# schematic.net
KiCad netlist of a schematic drawn in Altium Designer
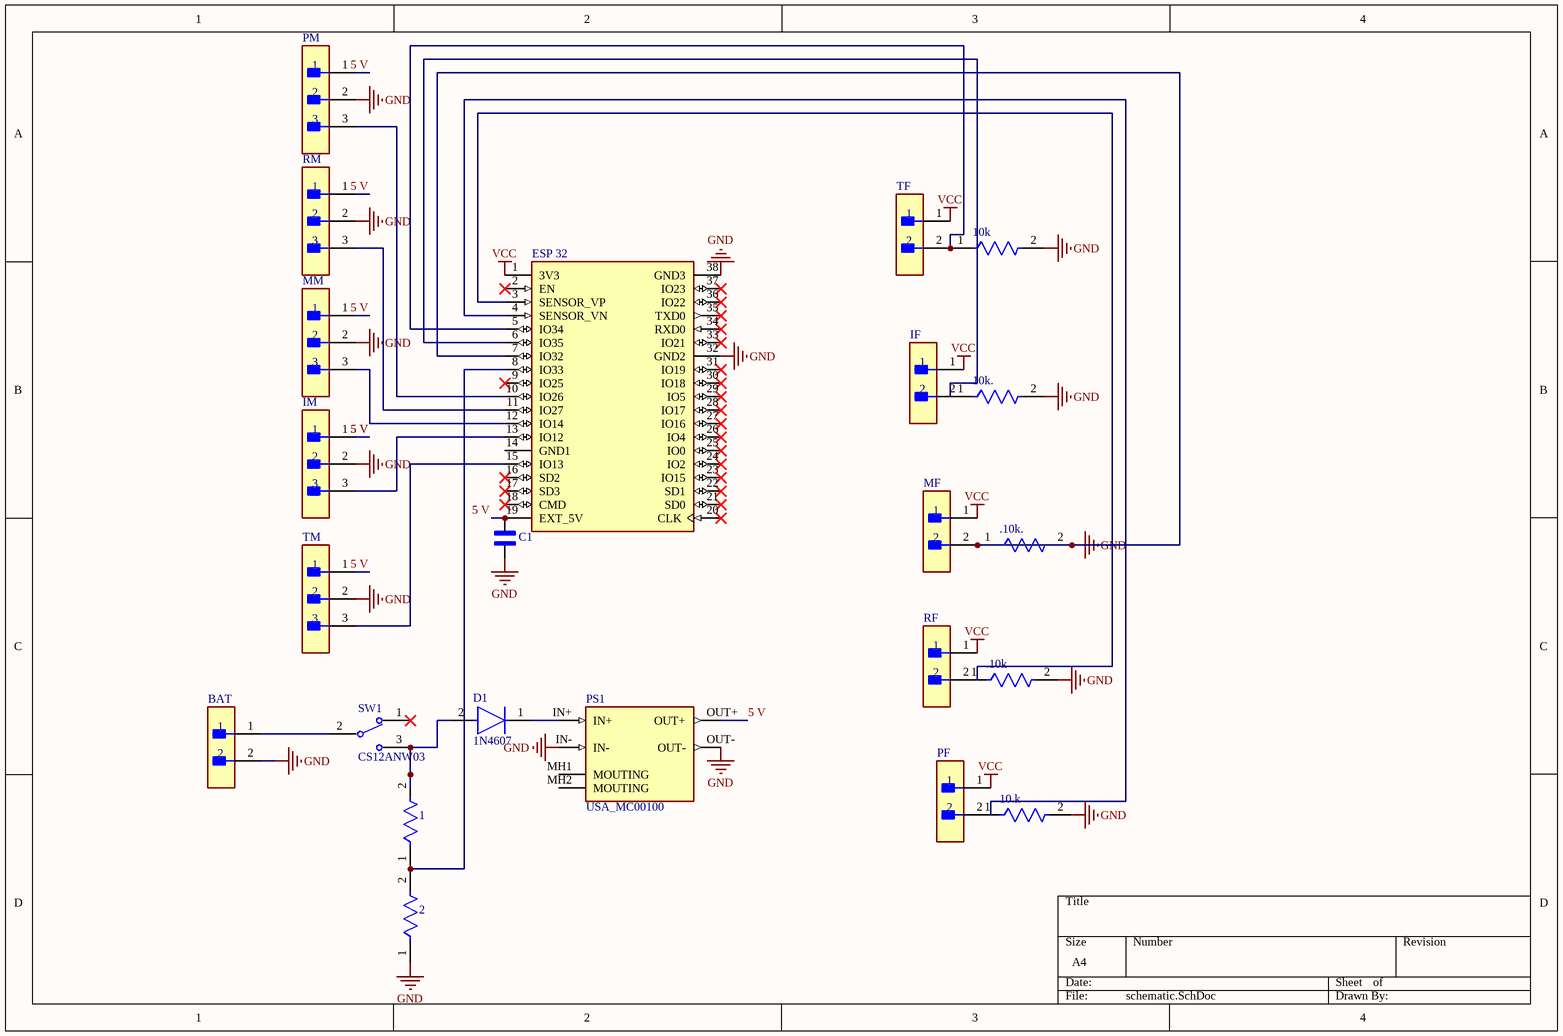
[diagram p0: schematic.SchDoc]

(export (version "E")
  (design (tool "Eeschema 10.0.6"))
  (components
    (comp (ref ".10k")
      (value "VR37000001204JA100")
      (footprint "FP-VR37-MFG")
      (description "RES 1.2M OHM 5% 1/2W AXIAL")
      (fields (field (name "TOLERANCE") "5%"))
      (libsource (lib "Altium Content Vault") (part "1029c3af85768c4190bb7ad29bc67b5"))
    )
    (comp (ref ".10k.")
      (value "VR37000001204JA100")
      (footprint "FP-VR37-MFG")
      (description "RES 1.2M OHM 5% 1/2W AXIAL")
      (fields (field (name "TOLERANCE") "5%"))
      (libsource (lib "Altium Content Vault") (part "1029c3af85768c4190bb7ad29bc67b5"))
    )
    (comp (ref "1")
      (value "VR37000001204JA100")
      (footprint "FP-VR37-MFG")
      (description "RES 1.2M OHM 5% 1/2W AXIAL")
      (fields (field (name "TOLERANCE") "5%"))
      (libsource (lib "Altium Content Vault") (part "1029c3af85768c4190bb7ad29bc67b5"))
    )
    (comp (ref "2")
      (value "VR37000001204JA100")
      (footprint "FP-VR37-MFG")
      (description "RES 1.2M OHM 5% 1/2W AXIAL")
      (fields (field (name "TOLERANCE") "5%"))
      (libsource (lib "Altium Content Vault") (part "1029c3af85768c4190bb7ad29bc67b5"))
    )
    (comp (ref "10.k")
      (value "VR37000001204JA100")
      (footprint "FP-VR37-MFG")
      (description "RES 1.2M OHM 5% 1/2W AXIAL")
      (fields (field (name "TOLERANCE") "5%"))
      (libsource (lib "Altium Content Vault") (part "1029c3af85768c4190bb7ad29bc67b5"))
    )
    (comp (ref "10k")
      (value "VR37000001204JA100")
      (footprint "FP-VR37-MFG")
      (description "RES 1.2M OHM 5% 1/2W AXIAL")
      (fields (field (name "TOLERANCE") "5%"))
      (libsource (lib "Altium Content Vault") (part "1029c3af85768c4190bb7ad29bc67b5"))
    )
    (comp (ref "10k.")
      (value "VR37000001204JA100")
      (footprint "FP-VR37-MFG")
      (description "RES 1.2M OHM 5% 1/2W AXIAL")
      (fields (field (name "TOLERANCE") "5%"))
      (libsource (lib "Altium Content Vault") (part "1029c3af85768c4190bb7ad29bc67b5"))
    )
    (comp (ref "BAT")
      (value "TSW-102-14-G-S")
      (footprint "FP-TSW-102-14-G-S-MFG")
      (description "CONN HEADER VERT 2POS 2.54MM")
      (libsource (lib "Altium Content Vault") (part "88c1139f9d239099ffebecbe3f7647a"))
    )
    (comp (ref "C1")
      (value "FA14X8R1H104KNU06")
      (footprint "CAPRB250W50L450T300H550")
      (description "0.1 ÂµF Â±10% 50V Ceramic Capacitor X8R Radial")
      (fields (field (name "MF") "TDK"))
      (libsource (lib "ceramic capacitor") (part "FA14X8R1H104KNU06"))
    )
    (comp (ref "D1")
      (value "1N4607")
      (footprint "FP-DO-35-MFG")
      (description "1N4607 1N4607 Series 85 V 0.2 A Axial Silicon Switching Diode - DO-35")
      (libsource (lib "Altium Content Vault") (part "1N4607"))
    )
    (comp (ref "ESP 32")
      (value "ESP32-DEVKITC")
      (footprint "MODULE_ESP32-DEVKITC")
      (description "Transceiver; 802.11 b/g/n (Wi-Fi, WiFi, WLAN), BluetoothÂ® Smart Ready 4.x Dual Mode")
      (fields (field (name "MF") "Espressif Systems") (field (name "MP") "ESP32-DEVKITC-32D-F"))
      (libsource (lib "ESP32-DEVKITC") (part "ESP32-DEVKITC"))
    )
    (comp (ref "IF")
      (value "TSW-102-14-G-S")
      (footprint "FP-TSW-102-14-G-S-MFG")
      (description "CONN HEADER VERT 2POS 2.54MM")
      (libsource (lib "Altium Content Vault") (part "88c1139f9d239099ffebecbe3f7647a"))
    )
    (comp (ref "IM")
      (value "NRPN031PAEN-RC")
      (footprint "FP-NRPN031PAEN-RC-MFG")
      (description "CONN HEADER VERT 3POS 2MM")
      (fields
        (field (name "OCTOPART") "https://octopart.com/nrpn031paen-rc-sullins-12817732")
        (field (name "MANUFACTURER") "Sullins")
      )
      (libsource (lib "Altium Content Vault") (part "0d3f023dd272f625e17a2be33dea85f"))
    )
    (comp (ref "MF")
      (value "TSW-102-14-G-S")
      (footprint "FP-TSW-102-14-G-S-MFG")
      (description "CONN HEADER VERT 2POS 2.54MM")
      (libsource (lib "Altium Content Vault") (part "88c1139f9d239099ffebecbe3f7647a"))
    )
    (comp (ref "MM")
      (value "NRPN031PAEN-RC")
      (footprint "FP-NRPN031PAEN-RC-MFG")
      (description "CONN HEADER VERT 3POS 2MM")
      (fields
        (field (name "OCTOPART") "https://octopart.com/nrpn031paen-rc-sullins-12817732")
        (field (name "MANUFACTURER") "Sullins")
      )
      (libsource (lib "Altium Content Vault") (part "0d3f023dd272f625e17a2be33dea85f"))
    )
    (comp (ref "PF")
      (value "TSW-102-14-G-S")
      (footprint "FP-TSW-102-14-G-S-MFG")
      (description "CONN HEADER VERT 2POS 2.54MM")
      (libsource (lib "Altium Content Vault") (part "88c1139f9d239099ffebecbe3f7647a"))
    )
    (comp (ref "PM")
      (value "NRPN031PAEN-RC")
      (footprint "FP-NRPN031PAEN-RC-MFG")
      (description "CONN HEADER VERT 3POS 2MM")
      (fields
        (field (name "OCTOPART") "https://octopart.com/nrpn031paen-rc-sullins-12817732")
        (field (name "MANUFACTURER") "Sullins")
      )
      (libsource (lib "Altium Content Vault") (part "0d3f023dd272f625e17a2be33dea85f"))
    )
    (comp (ref "PS1")
      (value "USA_MC00100")
      (footprint "CONV_USA_MC00100")
      (description "DC-DC LM2596 Step Down Adjustable Converter Power Supply Module 1.3V-35V")
      (fields (field (name "MF") "YKS"))
      (libsource (lib "BUCK CONVERTOR 1") (part "USA_MC00100"))
    )
    (comp (ref "RF")
      (value "TSW-102-14-G-S")
      (footprint "FP-TSW-102-14-G-S-MFG")
      (description "CONN HEADER VERT 2POS 2.54MM")
      (libsource (lib "Altium Content Vault") (part "88c1139f9d239099ffebecbe3f7647a"))
    )
    (comp (ref "RM")
      (value "NRPN031PAEN-RC")
      (footprint "FP-NRPN031PAEN-RC-MFG")
      (description "CONN HEADER VERT 3POS 2MM")
      (fields
        (field (name "OCTOPART") "https://octopart.com/nrpn031paen-rc-sullins-12817732")
        (field (name "MANUFACTURER") "Sullins")
      )
      (libsource (lib "Altium Content Vault") (part "0d3f023dd272f625e17a2be33dea85f"))
    )
    (comp (ref "SW1")
      (value "CS12ANW03")
      (footprint "FP-CS12ANW03-MFG")
      (description "SWITCH SLIDE SPDT 3A 125V")
      (libsource (lib "Altium Content Vault") (part "12161840acc88c497b895bf2e19a5b1"))
    )
    (comp (ref "TF")
      (value "TSW-102-14-G-S")
      (footprint "FP-TSW-102-14-G-S-MFG")
      (description "CONN HEADER VERT 2POS 2.54MM")
      (libsource (lib "Altium Content Vault") (part "88c1139f9d239099ffebecbe3f7647a"))
    )
    (comp (ref "TM")
      (value "NRPN031PAEN-RC")
      (footprint "FP-NRPN031PAEN-RC-MFG")
      (description "CONN HEADER VERT 3POS 2MM")
      (fields
        (field (name "OCTOPART") "https://octopart.com/nrpn031paen-rc-sullins-12817732")
        (field (name "MANUFACTURER") "Sullins")
      )
      (libsource (lib "Altium Content Vault") (part "0d3f023dd272f625e17a2be33dea85f"))
    )
  )
  (nets
    (net (code "1") (name "/5 V") (class "Default")
      (node (ref "C1") (pin "1") (pinfunction "1_1") (pintype "passive"))
      (node (ref "ESP 32") (pin "19") (pinfunction "EXT_5V_19") (pintype "power_in"))
      (node (ref "IM") (pin "1") (pinfunction "1_1") (pintype "passive"))
      (node (ref "MM") (pin "1") (pinfunction "1_1") (pintype "passive"))
      (node (ref "PM") (pin "1") (pinfunction "1_1") (pintype "passive"))
      (node (ref "PS1") (pin "OUT+") (pinfunction "OUT+_OUT+") (pintype "output"))
      (node (ref "RM") (pin "1") (pinfunction "1_1") (pintype "passive"))
      (node (ref "TM") (pin "1") (pinfunction "1_1") (pintype "passive"))
    )
    (net (code "2") (name "GND") (class "Default")
      (node (ref ".10k") (pin "2") (pinfunction "2_2") (pintype "passive"))
      (node (ref ".10k.") (pin "1") (pinfunction "1_1") (pintype "passive"))
      (node (ref ".10k.") (pin "2") (pinfunction "2_2") (pintype "passive"))
      (node (ref "10.k") (pin "2") (pinfunction "2_2") (pintype "passive"))
      (node (ref "10k") (pin "2") (pinfunction "2_2") (pintype "passive"))
      (node (ref "10k.") (pin "2") (pinfunction "2_2") (pintype "passive"))
      (node (ref "2") (pin "1") (pinfunction "1_1") (pintype "passive"))
      (node (ref "BAT") (pin "2") (pinfunction "2_2") (pintype "passive"))
      (node (ref "C1") (pin "2") (pinfunction "2_2") (pintype "passive"))
      (node (ref "ESP 32") (pin "32") (pinfunction "GND2_32") (pintype "power_in"))
      (node (ref "ESP 32") (pin "38") (pinfunction "GND3_38") (pintype "power_in"))
      (node (ref "ESP 32") (pin "7") (pinfunction "IO32_7") (pintype "bidirectional"))
      (node (ref "IM") (pin "2") (pinfunction "2_2") (pintype "passive"))
      (node (ref "MF") (pin "2") (pinfunction "2_2") (pintype "passive"))
      (node (ref "MM") (pin "2") (pinfunction "2_2") (pintype "passive"))
      (node (ref "PM") (pin "2") (pinfunction "2_2") (pintype "passive"))
      (node (ref "PS1") (pin "IN-") (pinfunction "IN-_IN-") (pintype "input"))
      (node (ref "PS1") (pin "OUT-") (pinfunction "OUT-_OUT-") (pintype "output"))
      (node (ref "RM") (pin "2") (pinfunction "2_2") (pintype "passive"))
      (node (ref "TM") (pin "2") (pinfunction "2_2") (pintype "passive"))
    )
    (net (code "3") (name "Net-(D1-A)") (class "Default")
      (node (ref "1") (pin "2") (pinfunction "2_2") (pintype "passive"))
      (node (ref "D1") (pin "2") (pinfunction "A_2") (pintype "passive"))
      (node (ref "SW1") (pin "3") (pinfunction "3_3") (pintype "passive"))
    )
    (net (code "4") (name "Net-(D1-C)") (class "Default")
      (node (ref "D1") (pin "1") (pinfunction "C_1") (pintype "passive"))
      (node (ref "PS1") (pin "IN+") (pinfunction "IN+_IN+") (pintype "input"))
    )
    (net (code "5") (name "Net-(ESP 32-IO12)") (class "Default")
      (node (ref "ESP 32") (pin "13") (pinfunction "IO12_13") (pintype "bidirectional"))
      (node (ref "IM") (pin "3") (pinfunction "3_3") (pintype "passive"))
    )
    (net (code "6") (name "Net-(ESP 32-IO13)") (class "Default")
      (node (ref "ESP 32") (pin "15") (pinfunction "IO13_15") (pintype "bidirectional"))
      (node (ref "TM") (pin "3") (pinfunction "3_3") (pintype "passive"))
    )
    (net (code "7") (name "Net-(ESP 32-IO14)") (class "Default")
      (node (ref "ESP 32") (pin "12") (pinfunction "IO14_12") (pintype "bidirectional"))
      (node (ref "MM") (pin "3") (pinfunction "3_3") (pintype "passive"))
    )
    (net (code "8") (name "Net-(ESP 32-IO26)") (class "Default")
      (node (ref "ESP 32") (pin "10") (pinfunction "IO26_10") (pintype "bidirectional"))
      (node (ref "PM") (pin "3") (pinfunction "3_3") (pintype "passive"))
    )
    (net (code "9") (name "Net-(ESP 32-IO27)") (class "Default")
      (node (ref "ESP 32") (pin "11") (pinfunction "IO27_11") (pintype "bidirectional"))
      (node (ref "RM") (pin "3") (pinfunction "3_3") (pintype "passive"))
    )
    (net (code "10") (name "Net-(ESP 32-IO33)") (class "Default")
      (node (ref "1") (pin "1") (pinfunction "1_1") (pintype "passive"))
      (node (ref "2") (pin "2") (pinfunction "2_2") (pintype "passive"))
      (node (ref "ESP 32") (pin "8") (pinfunction "IO33_8") (pintype "bidirectional"))
    )
    (net (code "11") (name "Net-(ESP 32-IO34)") (class "Default")
      (node (ref "10k") (pin "1") (pinfunction "1_1") (pintype "passive"))
      (node (ref "ESP 32") (pin "5") (pinfunction "IO34_5") (pintype "bidirectional"))
      (node (ref "TF") (pin "2") (pinfunction "2_2") (pintype "passive"))
    )
    (net (code "12") (name "Net-(ESP 32-IO35)") (class "Default")
      (node (ref "10k.") (pin "1") (pinfunction "1_1") (pintype "passive"))
      (node (ref "ESP 32") (pin "6") (pinfunction "IO35_6") (pintype "bidirectional"))
    )
    (net (code "13") (name "Net-(ESP 32-SENSOR_VN)") (class "Default")
      (node (ref "ESP 32") (pin "4") (pinfunction "SENSOR_VN_4") (pintype "input"))
      (node (ref "PF") (pin "2") (pinfunction "2_2") (pintype "passive"))
    )
    (net (code "14") (name "Net-(ESP 32-SENSOR_VP)") (class "Default")
      (node (ref "ESP 32") (pin "3") (pinfunction "SENSOR_VP_3") (pintype "input"))
      (node (ref "RF") (pin "2") (pinfunction "2_2") (pintype "passive"))
    )
    (net (code "15") (name "Net-(SW1-2(COM))") (class "Default")
      (node (ref "BAT") (pin "1") (pinfunction "1_1") (pintype "passive"))
      (node (ref "SW1") (pin "2") (pinfunction "2(COM)_2") (pintype "passive"))
    )
    (net (code "16") (name "VCC") (class "Default")
      (node (ref "ESP 32") (pin "1") (pinfunction "3V3_1") (pintype "power_in"))
      (node (ref "IF") (pin "1") (pinfunction "1_1") (pintype "passive"))
      (node (ref "MF") (pin "1") (pinfunction "1_1") (pintype "passive"))
      (node (ref "PF") (pin "1") (pinfunction "1_1") (pintype "passive"))
      (node (ref "RF") (pin "1") (pinfunction "1_1") (pintype "passive"))
      (node (ref "TF") (pin "1") (pinfunction "1_1") (pintype "passive"))
    )
    (net (code "17") (name "unconnected-(.10k-Pad1)") (class "Default")
      (node (ref ".10k") (pin "1") (pinfunction "1_1") (pintype "passive"))
    )
    (net (code "18") (name "unconnected-(10.k-Pad1)") (class "Default")
      (node (ref "10.k") (pin "1") (pinfunction "1_1") (pintype "passive"))
    )
    (net (code "19") (name "unconnected-(ESP 32-CLK-Pad20)") (class "Default")
      (node (ref "ESP 32") (pin "20") (pinfunction "CLK_20") (pintype "input+no_connect"))
    )
    (net (code "20") (name "unconnected-(ESP 32-CMD-Pad18)") (class "Default")
      (node (ref "ESP 32") (pin "18") (pinfunction "CMD_18") (pintype "bidirectional+no_connect"))
    )
    (net (code "21") (name "unconnected-(ESP 32-EN-Pad2)") (class "Default")
      (node (ref "ESP 32") (pin "2") (pinfunction "EN_2") (pintype "input+no_connect"))
    )
    (net (code "22") (name "unconnected-(ESP 32-GND1-Pad14)") (class "Default")
      (node (ref "ESP 32") (pin "14") (pinfunction "GND1_14") (pintype "power_in"))
    )
    (net (code "23") (name "unconnected-(ESP 32-IO0-Pad25)") (class "Default")
      (node (ref "ESP 32") (pin "25") (pinfunction "IO0_25") (pintype "bidirectional+no_connect"))
    )
    (net (code "24") (name "unconnected-(ESP 32-IO2-Pad24)") (class "Default")
      (node (ref "ESP 32") (pin "24") (pinfunction "IO2_24") (pintype "bidirectional+no_connect"))
    )
    (net (code "25") (name "unconnected-(ESP 32-IO4-Pad26)") (class "Default")
      (node (ref "ESP 32") (pin "26") (pinfunction "IO4_26") (pintype "bidirectional+no_connect"))
    )
    (net (code "26") (name "unconnected-(ESP 32-IO5-Pad29)") (class "Default")
      (node (ref "ESP 32") (pin "29") (pinfunction "IO5_29") (pintype "bidirectional+no_connect"))
    )
    (net (code "27") (name "unconnected-(ESP 32-IO15-Pad23)") (class "Default")
      (node (ref "ESP 32") (pin "23") (pinfunction "IO15_23") (pintype "bidirectional+no_connect"))
    )
    (net (code "28") (name "unconnected-(ESP 32-IO16-Pad27)") (class "Default")
      (node (ref "ESP 32") (pin "27") (pinfunction "IO16_27") (pintype "bidirectional+no_connect"))
    )
    (net (code "29") (name "unconnected-(ESP 32-IO17-Pad28)") (class "Default")
      (node (ref "ESP 32") (pin "28") (pinfunction "IO17_28") (pintype "bidirectional+no_connect"))
    )
    (net (code "30") (name "unconnected-(ESP 32-IO18-Pad30)") (class "Default")
      (node (ref "ESP 32") (pin "30") (pinfunction "IO18_30") (pintype "bidirectional+no_connect"))
    )
    (net (code "31") (name "unconnected-(ESP 32-IO19-Pad31)") (class "Default")
      (node (ref "ESP 32") (pin "31") (pinfunction "IO19_31") (pintype "bidirectional+no_connect"))
    )
    (net (code "32") (name "unconnected-(ESP 32-IO21-Pad33)") (class "Default")
      (node (ref "ESP 32") (pin "33") (pinfunction "IO21_33") (pintype "bidirectional+no_connect"))
    )
    (net (code "33") (name "unconnected-(ESP 32-IO22-Pad36)") (class "Default")
      (node (ref "ESP 32") (pin "36") (pinfunction "IO22_36") (pintype "bidirectional+no_connect"))
    )
    (net (code "34") (name "unconnected-(ESP 32-IO23-Pad37)") (class "Default")
      (node (ref "ESP 32") (pin "37") (pinfunction "IO23_37") (pintype "bidirectional+no_connect"))
    )
    (net (code "35") (name "unconnected-(ESP 32-IO25-Pad9)") (class "Default")
      (node (ref "ESP 32") (pin "9") (pinfunction "IO25_9") (pintype "bidirectional+no_connect"))
    )
    (net (code "36") (name "unconnected-(ESP 32-RXD0-Pad34)") (class "Default")
      (node (ref "ESP 32") (pin "34") (pinfunction "RXD0_34") (pintype "input+no_connect"))
    )
    (net (code "37") (name "unconnected-(ESP 32-SD0-Pad21)") (class "Default")
      (node (ref "ESP 32") (pin "21") (pinfunction "SD0_21") (pintype "bidirectional+no_connect"))
    )
    (net (code "38") (name "unconnected-(ESP 32-SD1-Pad22)") (class "Default")
      (node (ref "ESP 32") (pin "22") (pinfunction "SD1_22") (pintype "bidirectional+no_connect"))
    )
    (net (code "39") (name "unconnected-(ESP 32-SD2-Pad16)") (class "Default")
      (node (ref "ESP 32") (pin "16") (pinfunction "SD2_16") (pintype "bidirectional+no_connect"))
    )
    (net (code "40") (name "unconnected-(ESP 32-SD3-Pad17)") (class "Default")
      (node (ref "ESP 32") (pin "17") (pinfunction "SD3_17") (pintype "bidirectional+no_connect"))
    )
    (net (code "41") (name "unconnected-(ESP 32-TXD0-Pad35)") (class "Default")
      (node (ref "ESP 32") (pin "35") (pinfunction "TXD0_35") (pintype "output+no_connect"))
    )
    (net (code "42") (name "unconnected-(IF-Pad2)") (class "Default")
      (node (ref "IF") (pin "2") (pinfunction "2_2") (pintype "passive"))
    )
    (net (code "43") (name "unconnected-(PS1-MOUTING-PadMH1)") (class "Default")
      (node (ref "PS1") (pin "MH1") (pinfunction "MOUTING_MH1") (pintype "passive"))
    )
    (net (code "44") (name "unconnected-(PS1-MOUTING-PadMH2)") (class "Default")
      (node (ref "PS1") (pin "MH2") (pinfunction "MOUTING_MH2") (pintype "passive"))
    )
    (net (code "45") (name "unconnected-(SW1-Pad1)") (class "Default")
      (node (ref "SW1") (pin "1") (pinfunction "1_1") (pintype "passive+no_connect"))
    )
  )
)
